# Sheet1.net
KiCad netlist of a schematic drawn in Altium Designer
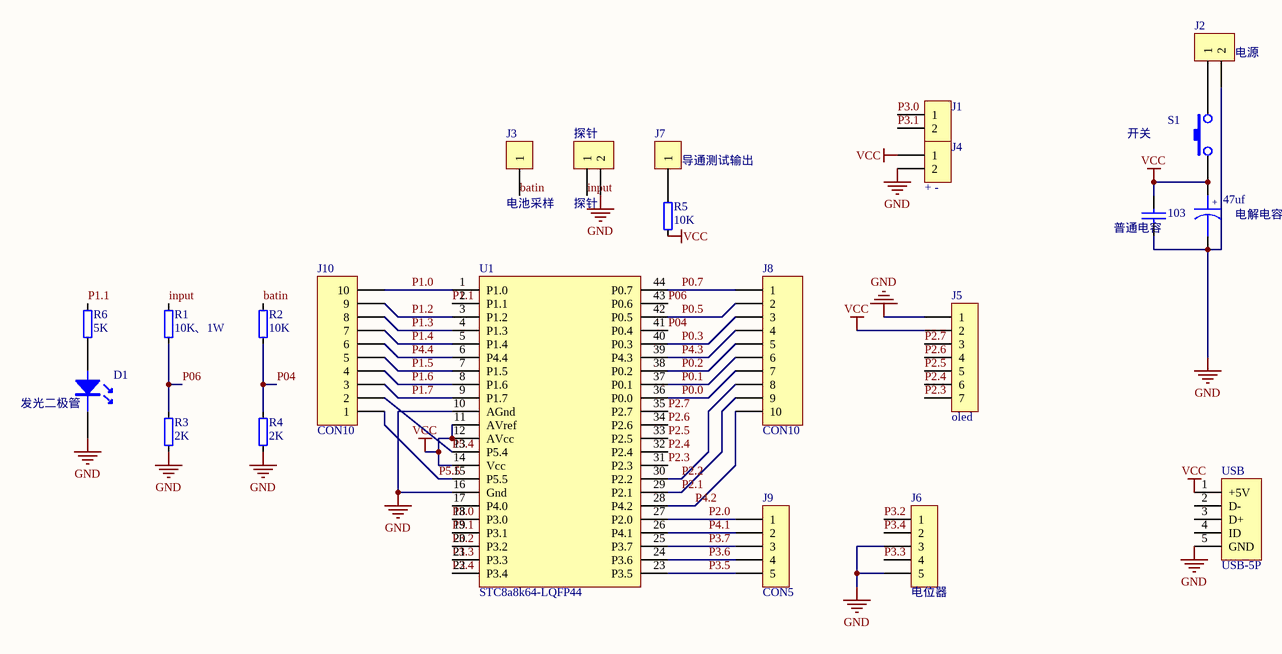
[diagram p0: Sheet1.SchDoc]

(export (version "E")
  (design (tool "Eeschema 10.0.6"))
  (components
    (comp (ref "47uf")
      (value "电解电容")
      (footprint "电解电容直插")
      (description "Capacitor")
      (libsource (lib "电容") (part "电解电容"))
    )
    (comp (ref "103")
      (value "普通电容")
      (footprint "瓷片电容直插")
      (description "Capacitor")
      (libsource (lib "电容") (part "普通电容"))
    )
    (comp (ref "D1") (value "发光二极管") (footprint "LED") (libsource (lib "Schlib1") (part "发光二极管")))
    (comp (ref "J1")
      (value "rxtx")
      (footprint "HDR2.54-LI-2P")
      (description "Connector")
      (libsource (lib "") (part "CON2_1"))
    )
    (comp (ref "J2")
      (value "电源")
      (footprint "HDR2.54-LI-2P")
      (description "Connector")
      (libsource (lib "Schlib1") (part "CON2"))
    )
    (comp (ref "J3")
      (value "电池采样")
      (footprint "1pin排针")
      (description "Connector")
      (libsource (lib "Schlib1") (part "CON1"))
    )
    (comp (ref "J4")
      (value "+ -")
      (footprint "HDR2.54-LI-2P")
      (description "Connector")
      (libsource (lib "") (part "CON2_1"))
    )
    (comp (ref "J5")
      (value "oled")
      (footprint "7pin排针")
      (description "Connector")
      (libsource (lib "Schlib1") (part "CON7"))
    )
    (comp (ref "J6")
      (value "电位器")
      (footprint "EC11")
      (description "Connector")
      (libsource (lib "Schlib1") (part "CON5"))
    )
    (comp (ref "J7")
      (value "导通测试输出")
      (footprint "1pin排针")
      (description "Connector")
      (libsource (lib "Schlib1") (part "CON1"))
    )
    (comp (ref "J8")
      (value "CON10")
      (footprint "HDR2.54-LI-10P")
      (description "Connector")
      (libsource (lib "") (part "CON10_1"))
    )
    (comp (ref "J9")
      (value "CON5")
      (footprint "HDR2.54-LI-5P")
      (description "Connector")
      (libsource (lib "插件") (part "CON5"))
    )
    (comp (ref "J10")
      (value "CON10")
      (footprint "HDR2.54-LI-10P")
      (description "Connector")
      (libsource (lib "插件") (part "CON10"))
    )
    (comp (ref "R1") (value "10K、1W") (footprint "直插电阻1/4W") (libsource (lib "Schlib1") (part "RES")))
    (comp (ref "R2") (value "10K") (footprint "直插电阻1/4W") (libsource (lib "Schlib1") (part "RES")))
    (comp (ref "R3") (value "2K") (footprint "直插电阻1/4W") (libsource (lib "Schlib1") (part "RES")))
    (comp (ref "R4") (value "2K") (footprint "直插电阻1/4W") (libsource (lib "Schlib1") (part "RES")))
    (comp (ref "R5") (value "10K") (footprint "直插电阻1/4W") (libsource (lib "Schlib1") (part "RES")))
    (comp (ref "R6") (value "5K") (footprint "直插电阻1/4W") (libsource (lib "Schlib1") (part "RES")))
    (comp (ref "S1") (value "开关") (footprint "SS-12D10") (libsource (lib "Schlib1") (part "微动开关")))
    (comp (ref "U1")
      (value "STC8a8k64-LQFP44")
      (footprint "TQFP44-10*10")
      (description "STC单片机")
      (libsource (lib "Schlib1") (part "STC8a8k64-LQFP44"))
    )
    (comp (ref "USB")
      (value "USB-5P")
      (footprint "USB-micro_A")
      (description "微型USB母座")
      (fields (field (name "版权归属") "源创客"))
      (libsource (lib "4.1   - 接口类") (part "USB-5P"))
    )
    (comp (ref "探针")
      (value "探针")
      (footprint "2pin-5mm")
      (description "Connector")
      (libsource (lib "Schlib1") (part "CON2"))
    )
  )
  (nets
    (net (code "1") (name "/P0.0") (class "Default")
      (node (ref "J8") (pin "7") (pinfunction "7_7") (pintype "passive"))
      (node (ref "U1") (pin "36") (pinfunction "P0.0_36") (pintype "passive"))
    )
    (net (code "2") (name "/P0.1") (class "Default")
      (node (ref "J8") (pin "6") (pinfunction "6_6") (pintype "passive"))
      (node (ref "U1") (pin "37") (pinfunction "P0.1_37") (pintype "passive"))
    )
    (net (code "3") (name "/P0.2") (class "Default")
      (node (ref "J8") (pin "5") (pinfunction "5_5") (pintype "passive"))
      (node (ref "U1") (pin "38") (pinfunction "P0.2_38") (pintype "passive"))
    )
    (net (code "4") (name "/P0.3") (class "Default")
      (node (ref "J8") (pin "3") (pinfunction "3_3") (pintype "passive"))
      (node (ref "U1") (pin "40") (pinfunction "P0.3_40") (pintype "passive"))
    )
    (net (code "5") (name "/P0.5") (class "Default")
      (node (ref "J8") (pin "2") (pinfunction "2_2") (pintype "passive"))
      (node (ref "U1") (pin "42") (pinfunction "P0.5_42") (pintype "passive"))
    )
    (net (code "6") (name "/P0.7") (class "Default")
      (node (ref "J8") (pin "1") (pinfunction "1_1") (pintype "passive"))
      (node (ref "U1") (pin "44") (pinfunction "P0.7_44") (pintype "passive"))
    )
    (net (code "7") (name "/P1.0") (class "Default")
      (node (ref "J10") (pin "10") (pinfunction "10_10") (pintype "passive"))
      (node (ref "U1") (pin "1") (pinfunction "P1.0_1") (pintype "passive"))
    )
    (net (code "8") (name "/P1.1") (class "Default")
      (node (ref "R6") (pin "2") (pinfunction "2_2") (pintype "passive"))
      (node (ref "U1") (pin "2") (pinfunction "P1.1_2") (pintype "passive"))
    )
    (net (code "9") (name "/P1.2") (class "Default")
      (node (ref "J10") (pin "9") (pinfunction "9_9") (pintype "passive"))
      (node (ref "U1") (pin "3") (pinfunction "P1.2_3") (pintype "passive"))
    )
    (net (code "10") (name "/P1.3") (class "Default")
      (node (ref "J10") (pin "8") (pinfunction "8_8") (pintype "passive"))
      (node (ref "U1") (pin "4") (pinfunction "P1.3_4") (pintype "passive"))
    )
    (net (code "11") (name "/P1.4") (class "Default")
      (node (ref "J10") (pin "7") (pinfunction "7_7") (pintype "passive"))
      (node (ref "U1") (pin "5") (pinfunction "P1.4_5") (pintype "passive"))
    )
    (net (code "12") (name "/P1.5") (class "Default")
      (node (ref "J10") (pin "5") (pinfunction "5_5") (pintype "passive"))
      (node (ref "U1") (pin "7") (pinfunction "P1.5_7") (pintype "passive"))
    )
    (net (code "13") (name "/P1.6") (class "Default")
      (node (ref "J10") (pin "4") (pinfunction "4_4") (pintype "passive"))
      (node (ref "U1") (pin "8") (pinfunction "P1.6_8") (pintype "passive"))
    )
    (net (code "14") (name "/P1.7") (class "Default")
      (node (ref "J10") (pin "3") (pinfunction "3_3") (pintype "passive"))
      (node (ref "U1") (pin "9") (pinfunction "P1.7_9") (pintype "passive"))
    )
    (net (code "15") (name "/P2.0") (class "Default")
      (node (ref "J9") (pin "1") (pinfunction "1_1") (pintype "passive"))
      (node (ref "U1") (pin "27") (pinfunction "P2.0_27") (pintype "passive"))
    )
    (net (code "16") (name "/P2.1") (class "Default")
      (node (ref "J8") (pin "9") (pinfunction "9_9") (pintype "passive"))
      (node (ref "U1") (pin "29") (pinfunction "P2.1_29") (pintype "passive"))
    )
    (net (code "17") (name "/P2.2") (class "Default")
      (node (ref "J8") (pin "8") (pinfunction "8_8") (pintype "passive"))
      (node (ref "U1") (pin "30") (pinfunction "P2.2_30") (pintype "passive"))
    )
    (net (code "18") (name "/P2.3") (class "Default")
      (node (ref "J5") (pin "7") (pinfunction "7_7") (pintype "passive"))
      (node (ref "U1") (pin "31") (pinfunction "P2.3_31") (pintype "passive"))
    )
    (net (code "19") (name "/P2.4") (class "Default")
      (node (ref "J5") (pin "6") (pinfunction "6_6") (pintype "passive"))
      (node (ref "U1") (pin "32") (pinfunction "P2.4_32") (pintype "passive"))
    )
    (net (code "20") (name "/P2.5") (class "Default")
      (node (ref "J5") (pin "5") (pinfunction "5_5") (pintype "passive"))
      (node (ref "U1") (pin "33") (pinfunction "P2.5_33") (pintype "passive"))
    )
    (net (code "21") (name "/P2.6") (class "Default")
      (node (ref "J5") (pin "4") (pinfunction "4_4") (pintype "passive"))
      (node (ref "U1") (pin "34") (pinfunction "P2.6_34") (pintype "passive"))
    )
    (net (code "22") (name "/P2.7") (class "Default")
      (node (ref "J5") (pin "3") (pinfunction "3_3") (pintype "passive"))
      (node (ref "U1") (pin "35") (pinfunction "P2.7_35") (pintype "passive"))
    )
    (net (code "23") (name "/P3.0") (class "Default")
      (node (ref "J1") (pin "1") (pinfunction "1_1") (pintype "passive"))
      (node (ref "U1") (pin "18") (pinfunction "P3.0_18") (pintype "passive"))
    )
    (net (code "24") (name "/P3.1") (class "Default")
      (node (ref "J1") (pin "2") (pinfunction "2_2") (pintype "passive"))
      (node (ref "U1") (pin "19") (pinfunction "P3.1_19") (pintype "passive"))
    )
    (net (code "25") (name "/P3.2") (class "Default")
      (node (ref "J6") (pin "1") (pinfunction "1_1") (pintype "passive"))
      (node (ref "U1") (pin "20") (pinfunction "P3.2_20") (pintype "passive"))
    )
    (net (code "26") (name "/P3.3") (class "Default")
      (node (ref "J6") (pin "4") (pinfunction "4_4") (pintype "passive"))
      (node (ref "U1") (pin "21") (pinfunction "P3.3_21") (pintype "passive"))
    )
    (net (code "27") (name "/P3.4") (class "Default")
      (node (ref "J6") (pin "2") (pinfunction "2_2") (pintype "passive"))
      (node (ref "U1") (pin "22") (pinfunction "P3.4_22") (pintype "passive"))
    )
    (net (code "28") (name "/P3.5") (class "Default")
      (node (ref "J9") (pin "5") (pinfunction "5_5") (pintype "passive"))
      (node (ref "U1") (pin "23") (pinfunction "P3.5_23") (pintype "passive"))
    )
    (net (code "29") (name "/P3.6") (class "Default")
      (node (ref "J9") (pin "4") (pinfunction "4_4") (pintype "passive"))
      (node (ref "U1") (pin "24") (pinfunction "P3.6_24") (pintype "passive"))
    )
    (net (code "30") (name "/P3.7") (class "Default")
      (node (ref "J9") (pin "3") (pinfunction "3_3") (pintype "passive"))
      (node (ref "U1") (pin "25") (pinfunction "P3.7_25") (pintype "passive"))
    )
    (net (code "31") (name "/P04") (class "Default")
      (node (ref "R2") (pin "1") (pinfunction "1_1") (pintype "passive"))
      (node (ref "R4") (pin "2") (pinfunction "2_2") (pintype "passive"))
      (node (ref "U1") (pin "41") (pinfunction "P0.4_41") (pintype "passive"))
    )
    (net (code "32") (name "/P4.1") (class "Default")
      (node (ref "J9") (pin "2") (pinfunction "2_2") (pintype "passive"))
      (node (ref "U1") (pin "26") (pinfunction "P4.1_26") (pintype "passive"))
    )
    (net (code "33") (name "/P4.2") (class "Default")
      (node (ref "J8") (pin "10") (pinfunction "10_10") (pintype "passive"))
      (node (ref "U1") (pin "28") (pinfunction "P4.2_28") (pintype "passive"))
    )
    (net (code "34") (name "/P4.3") (class "Default")
      (node (ref "J8") (pin "4") (pinfunction "4_4") (pintype "passive"))
      (node (ref "U1") (pin "39") (pinfunction "P4.3_39") (pintype "passive"))
    )
    (net (code "35") (name "/P4.4") (class "Default")
      (node (ref "J10") (pin "6") (pinfunction "6_6") (pintype "passive"))
      (node (ref "U1") (pin "6") (pinfunction "P4.4_6") (pintype "passive"))
    )
    (net (code "36") (name "/P5.4") (class "Default")
      (node (ref "J10") (pin "2") (pinfunction "2_2") (pintype "passive"))
      (node (ref "U1") (pin "13") (pinfunction "P5.4_13") (pintype "passive"))
    )
    (net (code "37") (name "/P5.5") (class "Default")
      (node (ref "J10") (pin "1") (pinfunction "1_1") (pintype "passive"))
      (node (ref "U1") (pin "15") (pinfunction "P5.5_15") (pintype "passive"))
    )
    (net (code "38") (name "/P06") (class "Default")
      (node (ref "R1") (pin "1") (pinfunction "1_1") (pintype "passive"))
      (node (ref "R3") (pin "2") (pinfunction "2_2") (pintype "passive"))
      (node (ref "U1") (pin "43") (pinfunction "P0.6_43") (pintype "passive"))
    )
    (net (code "39") (name "/batin") (class "Default")
      (node (ref "J3") (pin "1") (pinfunction "1_1") (pintype "passive"))
      (node (ref "R2") (pin "2") (pinfunction "2_2") (pintype "passive"))
    )
    (net (code "40") (name "/input") (class "Default")
      (node (ref "R1") (pin "2") (pinfunction "2_2") (pintype "passive"))
      (node (ref "探针") (pin "1") (pinfunction "1_1") (pintype "passive"))
    )
    (net (code "41") (name "GND") (class "Default")
      (node (ref "103") (pin "2") (pinfunction "2_2") (pintype "passive"))
      (node (ref "47uf") (pin "2") (pinfunction "2_2") (pintype "passive"))
      (node (ref "D1") (pin "K") (pinfunction "2_K") (pintype "passive"))
      (node (ref "J2") (pin "2") (pinfunction "2_2") (pintype "passive"))
      (node (ref "J4") (pin "2") (pinfunction "2_2") (pintype "passive"))
      (node (ref "J5") (pin "1") (pinfunction "1_1") (pintype "passive"))
      (node (ref "J6") (pin "3") (pinfunction "3_3") (pintype "passive"))
      (node (ref "J6") (pin "5") (pinfunction "5_5") (pintype "passive"))
      (node (ref "R3") (pin "1") (pinfunction "1_1") (pintype "passive"))
      (node (ref "R4") (pin "1") (pinfunction "1_1") (pintype "passive"))
      (node (ref "U1") (pin "10") (pinfunction "AGnd_10") (pintype "passive"))
      (node (ref "U1") (pin "16") (pinfunction "Gnd_16") (pintype "passive"))
      (node (ref "USB") (pin "5") (pinfunction "GND_5") (pintype "passive"))
      (node (ref "探针") (pin "2") (pinfunction "2_2") (pintype "passive"))
    )
    (net (code "42") (name "Net-(D1-1)") (class "Default")
      (node (ref "D1") (pin "A") (pinfunction "1_A") (pintype "passive"))
      (node (ref "R6") (pin "1") (pinfunction "1_1") (pintype "passive"))
    )
    (net (code "43") (name "Net-(J2-Pad1)") (class "Default")
      (node (ref "J2") (pin "1") (pinfunction "1_1") (pintype "passive"))
      (node (ref "S1") (pin "2") (pinfunction "2_2") (pintype "passive"))
    )
    (net (code "44") (name "Net-(J7-Pad1)") (class "Default")
      (node (ref "J7") (pin "1") (pinfunction "1_1") (pintype "passive"))
      (node (ref "R5") (pin "2") (pinfunction "2_2") (pintype "passive"))
    )
    (net (code "45") (name "VCC") (class "Default")
      (node (ref "103") (pin "1") (pinfunction "1_1") (pintype "passive"))
      (node (ref "47uf") (pin "1") (pinfunction "1_1") (pintype "passive"))
      (node (ref "J4") (pin "1") (pinfunction "1_1") (pintype "passive"))
      (node (ref "J5") (pin "2") (pinfunction "2_2") (pintype "passive"))
      (node (ref "R5") (pin "1") (pinfunction "1_1") (pintype "passive"))
      (node (ref "S1") (pin "1") (pinfunction "1_1") (pintype "passive"))
      (node (ref "U1") (pin "11") (pinfunction "AVref_11") (pintype "passive"))
      (node (ref "U1") (pin "12") (pinfunction "AVcc_12") (pintype "passive"))
      (node (ref "U1") (pin "14") (pinfunction "Vcc_14") (pintype "passive"))
      (node (ref "USB") (pin "1") (pinfunction "+5V_1") (pintype "passive"))
    )
    (net (code "46") (name "unconnected-(U1-P4.0-Pad17)") (class "Default")
      (node (ref "U1") (pin "17") (pinfunction "P4.0_17") (pintype "passive"))
    )
    (net (code "47") (name "unconnected-(USB-D+-Pad3)") (class "Default")
      (node (ref "USB") (pin "3") (pinfunction "D+_3") (pintype "passive"))
    )
    (net (code "48") (name "unconnected-(USB-D--Pad2)") (class "Default")
      (node (ref "USB") (pin "2") (pinfunction "D-_2") (pintype "passive"))
    )
    (net (code "49") (name "unconnected-(USB-ID-Pad4)") (class "Default")
      (node (ref "USB") (pin "4") (pinfunction "ID_4") (pintype "passive"))
    )
  )
)
